# SCH_2-way_Traffic.net
KiCad netlist of a schematic drawn in Altium Designer
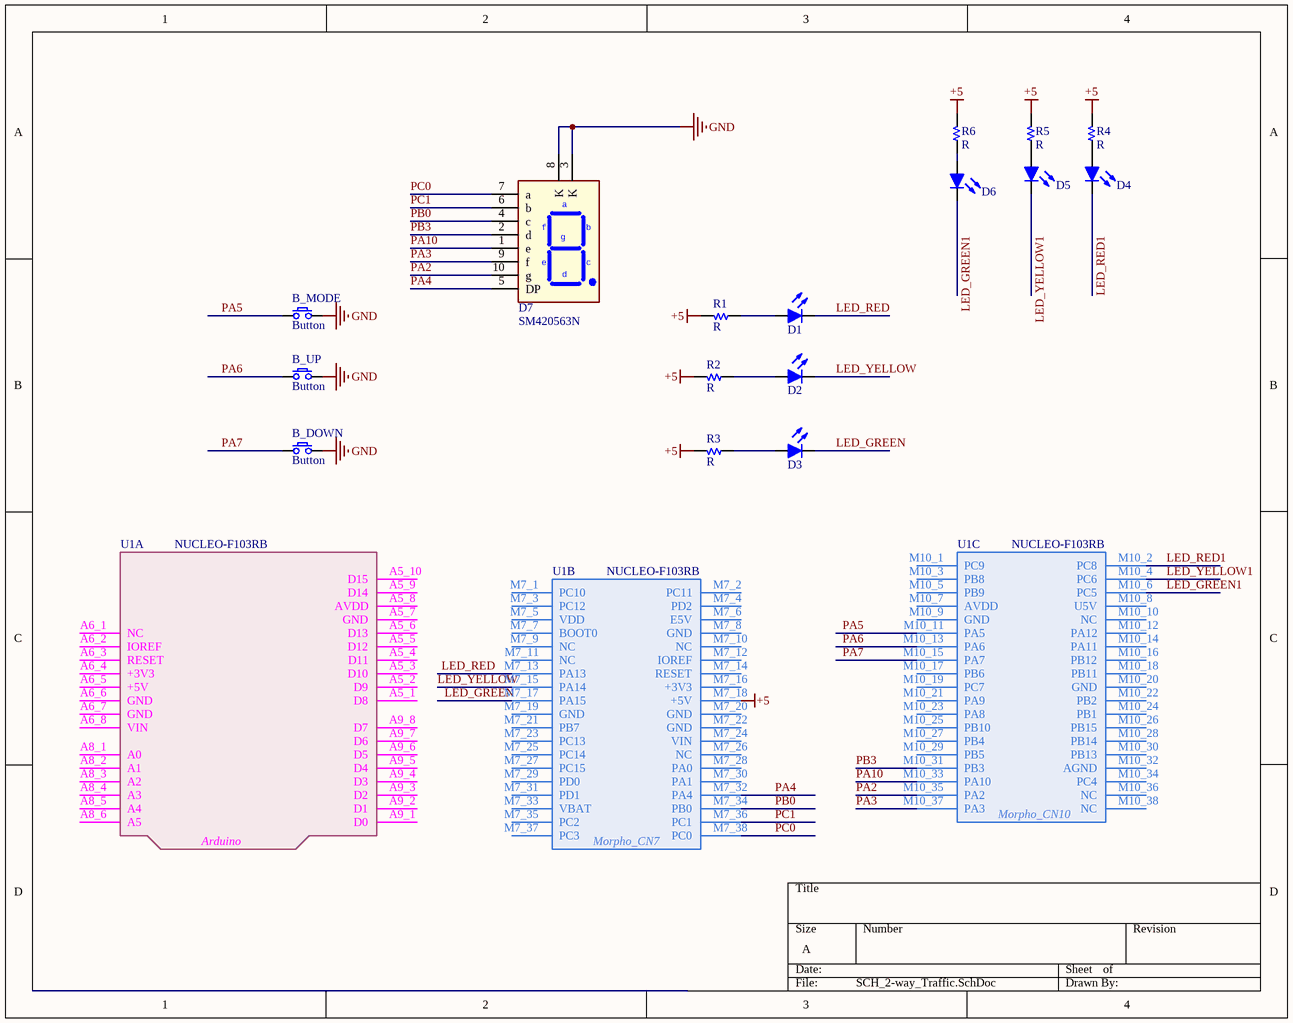
[diagram p0: SCH_2-way_Traffic.SchDoc]

(export (version "E")
  (design (tool "Eeschema 10.0.6"))
  (components
    (comp (ref "B_DOWN")
      (value "Button")
      (footprint "SW/2/DIP")
      (description "Tact switch 2 pin")
      (libsource (lib "chipfc_altium_libs") (part "SW SPST"))
    )
    (comp (ref "B_MODE")
      (value "Button")
      (footprint "SW/2/DIP")
      (description "Tact switch 2 pin")
      (libsource (lib "chipfc_altium_libs") (part "SW SPST"))
    )
    (comp (ref "B_UP")
      (value "Button")
      (footprint "SW/2/DIP")
      (description "Tact switch 2 pin")
      (libsource (lib "chipfc_altium_libs") (part "SW SPST"))
    )
    (comp (ref "D1")
      (value "Led")
      (footprint "LED 3MM - red")
      (description "Typical LED")
      (libsource (lib "chipfc_altium_libs") (part "Led"))
    )
    (comp (ref "D2")
      (value "Led")
      (footprint "LED 3MM - yellow")
      (description "Typical LED")
      (libsource (lib "chipfc_altium_libs") (part "Led"))
    )
    (comp (ref "D3")
      (value "Led")
      (footprint "LED 3MM - green")
      (description "Typical LED")
      (libsource (lib "chipfc_altium_libs") (part "Led"))
    )
    (comp (ref "D4")
      (value "Led")
      (footprint "LED 3MM - red")
      (description "Typical LED")
      (libsource (lib "chipfc_altium_libs") (part "Led"))
    )
    (comp (ref "D5")
      (value "Led")
      (footprint "LED 3MM - yellow")
      (description "Typical LED")
      (libsource (lib "chipfc_altium_libs") (part "Led"))
    )
    (comp (ref "D6")
      (value "Led")
      (footprint "LED 3MM - green")
      (description "Typical LED")
      (libsource (lib "chipfc_altium_libs") (part "Led"))
    )
    (comp (ref "D7")
      (value "SM420563N")
      (footprint "LED/7SEG/0.56")
      (description "SM420563N, Common-Cathode, LED 7-seg, RED, 0.56\",")
      (libsource (lib "bk2022") (part "LED 7-SEG SM420563N"))
    )
    (comp (ref "R1")
      (value "R")
      (footprint "R 0805")
      (description "Resistor")
      (libsource (lib "chipfc_altium_libs") (part "Resistor"))
    )
    (comp (ref "R2")
      (value "R")
      (footprint "R 0805")
      (description "Resistor")
      (libsource (lib "chipfc_altium_libs") (part "Resistor"))
    )
    (comp (ref "R3")
      (value "R")
      (footprint "R 0805")
      (description "Resistor")
      (libsource (lib "chipfc_altium_libs") (part "Resistor"))
    )
    (comp (ref "R4")
      (value "R")
      (footprint "R 0805")
      (description "Resistor")
      (libsource (lib "chipfc_altium_libs") (part "Resistor"))
    )
    (comp (ref "R5")
      (value "R")
      (footprint "R 0805")
      (description "Resistor")
      (libsource (lib "chipfc_altium_libs") (part "Resistor"))
    )
    (comp (ref "R6")
      (value "R")
      (footprint "R 0805")
      (description "Resistor")
      (libsource (lib "chipfc_altium_libs") (part "Resistor"))
    )
    (comp (ref "U1")
      (value "NUCLEO-F103RB")
      (footprint "NUCLEO")
      (fields (field (name "MANUFACTURER") "STMicroelectronics"))
      (libsource (lib "nucleo") (part "NUCLEO-F103RB"))
    )
  )
  (nets
    (net (code "1") (name "+5") (class "Default")
      (node (ref "R1") (pin "2") (pinfunction "2_2") (pintype "passive"))
      (node (ref "R2") (pin "2") (pinfunction "2_2") (pintype "passive"))
      (node (ref "R3") (pin "2") (pinfunction "2_2") (pintype "passive"))
      (node (ref "R4") (pin "2") (pinfunction "2_2") (pintype "passive"))
      (node (ref "R5") (pin "2") (pinfunction "2_2") (pintype "passive"))
      (node (ref "R6") (pin "2") (pinfunction "2_2") (pintype "passive"))
      (node (ref "U1") (pin "M7_18") (pinfunction "+5V_M7_18") (pintype "passive"))
    )
    (net (code "2") (name "/LED_GREEN") (class "Default")
      (node (ref "D3") (pin "2") (pinfunction "K_2") (pintype "passive"))
      (node (ref "U1") (pin "M7_17") (pinfunction "PA15_M7_17") (pintype "passive"))
    )
    (net (code "3") (name "/LED_GREEN1") (class "Default")
      (node (ref "D6") (pin "2") (pinfunction "K_2") (pintype "passive"))
      (node (ref "U1") (pin "M10_6") (pinfunction "PC5_M10_6") (pintype "passive"))
    )
    (net (code "4") (name "/LED_RED") (class "Default")
      (node (ref "D1") (pin "2") (pinfunction "K_2") (pintype "passive"))
      (node (ref "U1") (pin "M7_13") (pinfunction "PA13_M7_13") (pintype "passive"))
    )
    (net (code "5") (name "/LED_RED1") (class "Default")
      (node (ref "D4") (pin "2") (pinfunction "K_2") (pintype "passive"))
      (node (ref "U1") (pin "M10_2") (pinfunction "PC8_M10_2") (pintype "passive"))
    )
    (net (code "6") (name "/LED_YELLOW") (class "Default")
      (node (ref "D2") (pin "2") (pinfunction "K_2") (pintype "passive"))
      (node (ref "U1") (pin "M7_15") (pinfunction "PA14_M7_15") (pintype "passive"))
    )
    (net (code "7") (name "/LED_YELLOW1") (class "Default")
      (node (ref "D5") (pin "2") (pinfunction "K_2") (pintype "passive"))
      (node (ref "U1") (pin "M10_4") (pinfunction "PC6_M10_4") (pintype "passive"))
    )
    (net (code "8") (name "/PA2") (class "Default")
      (node (ref "D7") (pin "10") (pinfunction "g_10") (pintype "passive"))
      (node (ref "U1") (pin "M10_35") (pinfunction "PA2_M10_35") (pintype "passive"))
    )
    (net (code "9") (name "/PA3") (class "Default")
      (node (ref "D7") (pin "9") (pinfunction "f_9") (pintype "passive"))
      (node (ref "U1") (pin "M10_37") (pinfunction "PA3_M10_37") (pintype "passive"))
    )
    (net (code "10") (name "/PA4") (class "Default")
      (node (ref "D7") (pin "5") (pinfunction "DP_5") (pintype "passive"))
      (node (ref "U1") (pin "M7_32") (pinfunction "PA4_M7_32") (pintype "passive"))
    )
    (net (code "11") (name "/PA5") (class "Default")
      (node (ref "B_MODE") (pin "1") (pinfunction "1_1") (pintype "passive"))
      (node (ref "U1") (pin "M10_11") (pinfunction "PA5_M10_11") (pintype "passive"))
    )
    (net (code "12") (name "/PA6") (class "Default")
      (node (ref "B_UP") (pin "1") (pinfunction "1_1") (pintype "passive"))
      (node (ref "U1") (pin "M10_13") (pinfunction "PA6_M10_13") (pintype "passive"))
    )
    (net (code "13") (name "/PA7") (class "Default")
      (node (ref "B_DOWN") (pin "1") (pinfunction "1_1") (pintype "passive"))
      (node (ref "U1") (pin "M10_15") (pinfunction "PA7_M10_15") (pintype "passive"))
    )
    (net (code "14") (name "/PA10") (class "Default")
      (node (ref "D7") (pin "1") (pinfunction "e_1") (pintype "passive"))
      (node (ref "U1") (pin "M10_33") (pinfunction "PA10_M10_33") (pintype "passive"))
    )
    (net (code "15") (name "/PB0") (class "Default")
      (node (ref "D7") (pin "4") (pinfunction "c_4") (pintype "passive"))
      (node (ref "U1") (pin "M7_34") (pinfunction "PB0_M7_34") (pintype "passive"))
    )
    (net (code "16") (name "/PB3") (class "Default")
      (node (ref "D7") (pin "2") (pinfunction "d_2") (pintype "passive"))
      (node (ref "U1") (pin "M10_31") (pinfunction "PB3_M10_31") (pintype "passive"))
    )
    (net (code "17") (name "/PC0") (class "Default")
      (node (ref "D7") (pin "7") (pinfunction "a_7") (pintype "passive"))
      (node (ref "U1") (pin "M7_38") (pinfunction "PC0_M7_38") (pintype "passive"))
    )
    (net (code "18") (name "/PC1") (class "Default")
      (node (ref "D7") (pin "6") (pinfunction "b_6") (pintype "passive"))
      (node (ref "U1") (pin "M7_36") (pinfunction "PC1_M7_36") (pintype "passive"))
    )
    (net (code "19") (name "GND") (class "Default")
      (node (ref "B_DOWN") (pin "2") (pinfunction "2_2") (pintype "passive"))
      (node (ref "B_MODE") (pin "2") (pinfunction "2_2") (pintype "passive"))
      (node (ref "B_UP") (pin "2") (pinfunction "2_2") (pintype "passive"))
      (node (ref "D7") (pin "3") (pinfunction "K_3") (pintype "passive"))
      (node (ref "D7") (pin "8") (pinfunction "K_8") (pintype "passive"))
    )
    (net (code "20") (name "Net-(D1-A)") (class "Default")
      (node (ref "D1") (pin "1") (pinfunction "A_1") (pintype "passive"))
      (node (ref "R1") (pin "1") (pinfunction "1_1") (pintype "passive"))
    )
    (net (code "21") (name "Net-(D2-A)") (class "Default")
      (node (ref "D2") (pin "1") (pinfunction "A_1") (pintype "passive"))
      (node (ref "R2") (pin "1") (pinfunction "1_1") (pintype "passive"))
    )
    (net (code "22") (name "Net-(D3-A)") (class "Default")
      (node (ref "D3") (pin "1") (pinfunction "A_1") (pintype "passive"))
      (node (ref "R3") (pin "1") (pinfunction "1_1") (pintype "passive"))
    )
    (net (code "23") (name "Net-(D4-A)") (class "Default")
      (node (ref "D4") (pin "1") (pinfunction "A_1") (pintype "passive"))
      (node (ref "R4") (pin "1") (pinfunction "1_1") (pintype "passive"))
    )
    (net (code "24") (name "Net-(D5-A)") (class "Default")
      (node (ref "D5") (pin "1") (pinfunction "A_1") (pintype "passive"))
      (node (ref "R5") (pin "1") (pinfunction "1_1") (pintype "passive"))
    )
    (net (code "25") (name "Net-(D6-A)") (class "Default")
      (node (ref "D6") (pin "1") (pinfunction "A_1") (pintype "passive"))
      (node (ref "R6") (pin "1") (pinfunction "1_1") (pintype "passive"))
    )
    (net (code "26") (name "unconnected-(U1A-+3V3-PadA6_4)") (class "Default")
      (node (ref "U1") (pin "A6_4") (pinfunction "+3V3_A6_4") (pintype "passive"))
    )
    (net (code "27") (name "unconnected-(U1A-+5V-PadA6_5)") (class "Default")
      (node (ref "U1") (pin "A6_5") (pinfunction "+5V_A6_5") (pintype "passive"))
    )
    (net (code "28") (name "unconnected-(U1A-A0-PadA8_1)") (class "Default")
      (node (ref "U1") (pin "A8_1") (pinfunction "A0_A8_1") (pintype "passive"))
    )
    (net (code "29") (name "unconnected-(U1A-A1-PadA8_2)") (class "Default")
      (node (ref "U1") (pin "A8_2") (pinfunction "A1_A8_2") (pintype "passive"))
    )
    (net (code "30") (name "unconnected-(U1A-A2-PadA8_3)") (class "Default")
      (node (ref "U1") (pin "A8_3") (pinfunction "A2_A8_3") (pintype "passive"))
    )
    (net (code "31") (name "unconnected-(U1A-A3-PadA8_4)") (class "Default")
      (node (ref "U1") (pin "A8_4") (pinfunction "A3_A8_4") (pintype "passive"))
    )
    (net (code "32") (name "unconnected-(U1A-A4-PadA8_5)") (class "Default")
      (node (ref "U1") (pin "A8_5") (pinfunction "A4_A8_5") (pintype "passive"))
    )
    (net (code "33") (name "unconnected-(U1A-A5-PadA8_6)") (class "Default")
      (node (ref "U1") (pin "A8_6") (pinfunction "A5_A8_6") (pintype "passive"))
    )
    (net (code "34") (name "unconnected-(U1A-AVDD-PadA5_8)") (class "Default")
      (node (ref "U1") (pin "A5_8") (pinfunction "AVDD_A5_8") (pintype "passive"))
    )
    (net (code "35") (name "unconnected-(U1A-D0-PadA9_1)") (class "Default")
      (node (ref "U1") (pin "A9_1") (pinfunction "D0_A9_1") (pintype "passive"))
    )
    (net (code "36") (name "unconnected-(U1A-D1-PadA9_2)") (class "Default")
      (node (ref "U1") (pin "A9_2") (pinfunction "D1_A9_2") (pintype "passive"))
    )
    (net (code "37") (name "unconnected-(U1A-D2-PadA9_3)") (class "Default")
      (node (ref "U1") (pin "A9_3") (pinfunction "D2_A9_3") (pintype "passive"))
    )
    (net (code "38") (name "unconnected-(U1A-D3-PadA9_4)") (class "Default")
      (node (ref "U1") (pin "A9_4") (pinfunction "D3_A9_4") (pintype "passive"))
    )
    (net (code "39") (name "unconnected-(U1A-D4-PadA9_5)") (class "Default")
      (node (ref "U1") (pin "A9_5") (pinfunction "D4_A9_5") (pintype "passive"))
    )
    (net (code "40") (name "unconnected-(U1A-D5-PadA9_6)") (class "Default")
      (node (ref "U1") (pin "A9_6") (pinfunction "D5_A9_6") (pintype "passive"))
    )
    (net (code "41") (name "unconnected-(U1A-D6-PadA9_7)") (class "Default")
      (node (ref "U1") (pin "A9_7") (pinfunction "D6_A9_7") (pintype "passive"))
    )
    (net (code "42") (name "unconnected-(U1A-D7-PadA9_8)") (class "Default")
      (node (ref "U1") (pin "A9_8") (pinfunction "D7_A9_8") (pintype "passive"))
    )
    (net (code "43") (name "unconnected-(U1A-D8-PadA5_1)") (class "Default")
      (node (ref "U1") (pin "A5_1") (pinfunction "D8_A5_1") (pintype "passive"))
    )
    (net (code "44") (name "unconnected-(U1A-D9-PadA5_2)") (class "Default")
      (node (ref "U1") (pin "A5_2") (pinfunction "D9_A5_2") (pintype "passive"))
    )
    (net (code "45") (name "unconnected-(U1A-D10-PadA5_3)") (class "Default")
      (node (ref "U1") (pin "A5_3") (pinfunction "D10_A5_3") (pintype "passive"))
    )
    (net (code "46") (name "unconnected-(U1A-D11-PadA5_4)") (class "Default")
      (node (ref "U1") (pin "A5_4") (pinfunction "D11_A5_4") (pintype "passive"))
    )
    (net (code "47") (name "unconnected-(U1A-D12-PadA5_5)") (class "Default")
      (node (ref "U1") (pin "A5_5") (pinfunction "D12_A5_5") (pintype "passive"))
    )
    (net (code "48") (name "unconnected-(U1A-D13-PadA5_6)") (class "Default")
      (node (ref "U1") (pin "A5_6") (pinfunction "D13_A5_6") (pintype "passive"))
    )
    (net (code "49") (name "unconnected-(U1A-D14-PadA5_9)") (class "Default")
      (node (ref "U1") (pin "A5_9") (pinfunction "D14_A5_9") (pintype "passive"))
    )
    (net (code "50") (name "unconnected-(U1A-D15-PadA5_10)") (class "Default")
      (node (ref "U1") (pin "A5_10") (pinfunction "D15_A5_10") (pintype "passive"))
    )
    (net (code "51") (name "unconnected-(U1A-GND-PadA5_7)") (class "Default")
      (node (ref "U1") (pin "A5_7") (pinfunction "GND_A5_7") (pintype "passive"))
    )
    (net (code "52") (name "unconnected-(U1A-GND-PadA6_6)") (class "Default")
      (node (ref "U1") (pin "A6_6") (pinfunction "GND_A6_6") (pintype "passive"))
    )
    (net (code "53") (name "unconnected-(U1A-GND-PadA6_7)") (class "Default")
      (node (ref "U1") (pin "A6_7") (pinfunction "GND_A6_7") (pintype "passive"))
    )
    (net (code "54") (name "unconnected-(U1A-IOREF-PadA6_2)") (class "Default")
      (node (ref "U1") (pin "A6_2") (pinfunction "IOREF_A6_2") (pintype "passive"))
    )
    (net (code "55") (name "unconnected-(U1A-NC-PadA6_1)") (class "Default")
      (node (ref "U1") (pin "A6_1") (pinfunction "NC_A6_1") (pintype "passive"))
    )
    (net (code "56") (name "unconnected-(U1A-RESET-PadA6_3)") (class "Default")
      (node (ref "U1") (pin "A6_3") (pinfunction "RESET_A6_3") (pintype "passive"))
    )
    (net (code "57") (name "unconnected-(U1A-VIN-PadA6_8)") (class "Default")
      (node (ref "U1") (pin "A6_8") (pinfunction "VIN_A6_8") (pintype "passive"))
    )
    (net (code "58") (name "unconnected-(U1B-+3V3-PadM7_16)") (class "Default")
      (node (ref "U1") (pin "M7_16") (pinfunction "+3V3_M7_16") (pintype "passive"))
    )
    (net (code "59") (name "unconnected-(U1B-BOOT0-PadM7_7)") (class "Default")
      (node (ref "U1") (pin "M7_7") (pinfunction "BOOT0_M7_7") (pintype "passive"))
    )
    (net (code "60") (name "unconnected-(U1B-E5V-PadM7_6)") (class "Default")
      (node (ref "U1") (pin "M7_6") (pinfunction "E5V_M7_6") (pintype "passive"))
    )
    (net (code "61") (name "unconnected-(U1B-GND-PadM7_8)") (class "Default")
      (node (ref "U1") (pin "M7_8") (pinfunction "GND_M7_8") (pintype "passive"))
    )
    (net (code "62") (name "unconnected-(U1B-GND-PadM7_19)") (class "Default")
      (node (ref "U1") (pin "M7_19") (pinfunction "GND_M7_19") (pintype "passive"))
    )
    (net (code "63") (name "unconnected-(U1B-GND-PadM7_20)") (class "Default")
      (node (ref "U1") (pin "M7_20") (pinfunction "GND_M7_20") (pintype "passive"))
    )
    (net (code "64") (name "unconnected-(U1B-GND-PadM7_22)") (class "Default")
      (node (ref "U1") (pin "M7_22") (pinfunction "GND_M7_22") (pintype "passive"))
    )
    (net (code "65") (name "unconnected-(U1B-IOREF-PadM7_12)") (class "Default")
      (node (ref "U1") (pin "M7_12") (pinfunction "IOREF_M7_12") (pintype "passive"))
    )
    (net (code "66") (name "unconnected-(U1B-NC-PadM7_9)") (class "Default")
      (node (ref "U1") (pin "M7_9") (pinfunction "NC_M7_9") (pintype "passive"))
    )
    (net (code "67") (name "unconnected-(U1B-NC-PadM7_10)") (class "Default")
      (node (ref "U1") (pin "M7_10") (pinfunction "NC_M7_10") (pintype "passive"))
    )
    (net (code "68") (name "unconnected-(U1B-NC-PadM7_11)") (class "Default")
      (node (ref "U1") (pin "M7_11") (pinfunction "NC_M7_11") (pintype "passive"))
    )
    (net (code "69") (name "unconnected-(U1B-NC-PadM7_26)") (class "Default")
      (node (ref "U1") (pin "M7_26") (pinfunction "NC_M7_26") (pintype "passive"))
    )
    (net (code "70") (name "unconnected-(U1B-PA0-PadM7_28)") (class "Default")
      (node (ref "U1") (pin "M7_28") (pinfunction "PA0_M7_28") (pintype "passive"))
    )
    (net (code "71") (name "unconnected-(U1B-PA1-PadM7_30)") (class "Default")
      (node (ref "U1") (pin "M7_30") (pinfunction "PA1_M7_30") (pintype "passive"))
    )
    (net (code "72") (name "unconnected-(U1B-PB7-PadM7_21)") (class "Default")
      (node (ref "U1") (pin "M7_21") (pinfunction "PB7_M7_21") (pintype "passive"))
    )
    (net (code "73") (name "unconnected-(U1B-PC2-PadM7_35)") (class "Default")
      (node (ref "U1") (pin "M7_35") (pinfunction "PC2_M7_35") (pintype "passive"))
    )
    (net (code "74") (name "unconnected-(U1B-PC3-PadM7_37)") (class "Default")
      (node (ref "U1") (pin "M7_37") (pinfunction "PC3_M7_37") (pintype "passive"))
    )
    (net (code "75") (name "unconnected-(U1B-PC10-PadM7_1)") (class "Default")
      (node (ref "U1") (pin "M7_1") (pinfunction "PC10_M7_1") (pintype "passive"))
    )
    (net (code "76") (name "unconnected-(U1B-PC11-PadM7_2)") (class "Default")
      (node (ref "U1") (pin "M7_2") (pinfunction "PC11_M7_2") (pintype "passive"))
    )
    (net (code "77") (name "unconnected-(U1B-PC12-PadM7_3)") (class "Default")
      (node (ref "U1") (pin "M7_3") (pinfunction "PC12_M7_3") (pintype "passive"))
    )
    (net (code "78") (name "unconnected-(U1B-PC13-PadM7_23)") (class "Default")
      (node (ref "U1") (pin "M7_23") (pinfunction "PC13_M7_23") (pintype "passive"))
    )
    (net (code "79") (name "unconnected-(U1B-PC14-PadM7_25)") (class "Default")
      (node (ref "U1") (pin "M7_25") (pinfunction "PC14_M7_25") (pintype "passive"))
    )
    (net (code "80") (name "unconnected-(U1B-PC15-PadM7_27)") (class "Default")
      (node (ref "U1") (pin "M7_27") (pinfunction "PC15_M7_27") (pintype "passive"))
    )
    (net (code "81") (name "unconnected-(U1B-PD0-PadM7_29)") (class "Default")
      (node (ref "U1") (pin "M7_29") (pinfunction "PD0_M7_29") (pintype "passive"))
    )
    (net (code "82") (name "unconnected-(U1B-PD1-PadM7_31)") (class "Default")
      (node (ref "U1") (pin "M7_31") (pinfunction "PD1_M7_31") (pintype "passive"))
    )
    (net (code "83") (name "unconnected-(U1B-PD2-PadM7_4)") (class "Default")
      (node (ref "U1") (pin "M7_4") (pinfunction "PD2_M7_4") (pintype "passive"))
    )
    (net (code "84") (name "unconnected-(U1B-RESET-PadM7_14)") (class "Default")
      (node (ref "U1") (pin "M7_14") (pinfunction "RESET_M7_14") (pintype "passive"))
    )
    (net (code "85") (name "unconnected-(U1B-VBAT-PadM7_33)") (class "Default")
      (node (ref "U1") (pin "M7_33") (pinfunction "VBAT_M7_33") (pintype "passive"))
    )
    (net (code "86") (name "unconnected-(U1B-VDD-PadM7_5)") (class "Default")
      (node (ref "U1") (pin "M7_5") (pinfunction "VDD_M7_5") (pintype "passive"))
    )
    (net (code "87") (name "unconnected-(U1B-VIN-PadM7_24)") (class "Default")
      (node (ref "U1") (pin "M7_24") (pinfunction "VIN_M7_24") (pintype "passive"))
    )
    (net (code "88") (name "unconnected-(U1C-AGND-PadM10_32)") (class "Default")
      (node (ref "U1") (pin "M10_32") (pinfunction "AGND_M10_32") (pintype "passive"))
    )
    (net (code "89") (name "unconnected-(U1C-AVDD-PadM10_7)") (class "Default")
      (node (ref "U1") (pin "M10_7") (pinfunction "AVDD_M10_7") (pintype "passive"))
    )
    (net (code "90") (name "unconnected-(U1C-GND-PadM10_9)") (class "Default")
      (node (ref "U1") (pin "M10_9") (pinfunction "GND_M10_9") (pintype "passive"))
    )
    (net (code "91") (name "unconnected-(U1C-GND-PadM10_20)") (class "Default")
      (node (ref "U1") (pin "M10_20") (pinfunction "GND_M10_20") (pintype "passive"))
    )
    (net (code "92") (name "unconnected-(U1C-NC-PadM10_10)") (class "Default")
      (node (ref "U1") (pin "M10_10") (pinfunction "NC_M10_10") (pintype "passive"))
    )
    (net (code "93") (name "unconnected-(U1C-NC-PadM10_36)") (class "Default")
      (node (ref "U1") (pin "M10_36") (pinfunction "NC_M10_36") (pintype "passive"))
    )
    (net (code "94") (name "unconnected-(U1C-NC-PadM10_38)") (class "Default")
      (node (ref "U1") (pin "M10_38") (pinfunction "NC_M10_38") (pintype "passive"))
    )
    (net (code "95") (name "unconnected-(U1C-PA8-PadM10_23)") (class "Default")
      (node (ref "U1") (pin "M10_23") (pinfunction "PA8_M10_23") (pintype "passive"))
    )
    (net (code "96") (name "unconnected-(U1C-PA9-PadM10_21)") (class "Default")
      (node (ref "U1") (pin "M10_21") (pinfunction "PA9_M10_21") (pintype "passive"))
    )
    (net (code "97") (name "unconnected-(U1C-PA11-PadM10_14)") (class "Default")
      (node (ref "U1") (pin "M10_14") (pinfunction "PA11_M10_14") (pintype "passive"))
    )
    (net (code "98") (name "unconnected-(U1C-PA12-PadM10_12)") (class "Default")
      (node (ref "U1") (pin "M10_12") (pinfunction "PA12_M10_12") (pintype "passive"))
    )
    (net (code "99") (name "unconnected-(U1C-PB1-PadM10_24)") (class "Default")
      (node (ref "U1") (pin "M10_24") (pinfunction "PB1_M10_24") (pintype "passive"))
    )
    (net (code "100") (name "unconnected-(U1C-PB2-PadM10_22)") (class "Default")
      (node (ref "U1") (pin "M10_22") (pinfunction "PB2_M10_22") (pintype "passive"))
    )
    (net (code "101") (name "unconnected-(U1C-PB4-PadM10_27)") (class "Default")
      (node (ref "U1") (pin "M10_27") (pinfunction "PB4_M10_27") (pintype "passive"))
    )
    (net (code "102") (name "unconnected-(U1C-PB5-PadM10_29)") (class "Default")
      (node (ref "U1") (pin "M10_29") (pinfunction "PB5_M10_29") (pintype "passive"))
    )
    (net (code "103") (name "unconnected-(U1C-PB6-PadM10_17)") (class "Default")
      (node (ref "U1") (pin "M10_17") (pinfunction "PB6_M10_17") (pintype "passive"))
    )
    (net (code "104") (name "unconnected-(U1C-PB8-PadM10_3)") (class "Default")
      (node (ref "U1") (pin "M10_3") (pinfunction "PB8_M10_3") (pintype "passive"))
    )
    (net (code "105") (name "unconnected-(U1C-PB9-PadM10_5)") (class "Default")
      (node (ref "U1") (pin "M10_5") (pinfunction "PB9_M10_5") (pintype "passive"))
    )
    (net (code "106") (name "unconnected-(U1C-PB10-PadM10_25)") (class "Default")
      (node (ref "U1") (pin "M10_25") (pinfunction "PB10_M10_25") (pintype "passive"))
    )
    (net (code "107") (name "unconnected-(U1C-PB11-PadM10_18)") (class "Default")
      (node (ref "U1") (pin "M10_18") (pinfunction "PB11_M10_18") (pintype "passive"))
    )
    (net (code "108") (name "unconnected-(U1C-PB12-PadM10_16)") (class "Default")
      (node (ref "U1") (pin "M10_16") (pinfunction "PB12_M10_16") (pintype "passive"))
    )
    (net (code "109") (name "unconnected-(U1C-PB13-PadM10_30)") (class "Default")
      (node (ref "U1") (pin "M10_30") (pinfunction "PB13_M10_30") (pintype "passive"))
    )
    (net (code "110") (name "unconnected-(U1C-PB14-PadM10_28)") (class "Default")
      (node (ref "U1") (pin "M10_28") (pinfunction "PB14_M10_28") (pintype "passive"))
    )
    (net (code "111") (name "unconnected-(U1C-PB15-PadM10_26)") (class "Default")
      (node (ref "U1") (pin "M10_26") (pinfunction "PB15_M10_26") (pintype "passive"))
    )
    (net (code "112") (name "unconnected-(U1C-PC4-PadM10_34)") (class "Default")
      (node (ref "U1") (pin "M10_34") (pinfunction "PC4_M10_34") (pintype "passive"))
    )
    (net (code "113") (name "unconnected-(U1C-PC7-PadM10_19)") (class "Default")
      (node (ref "U1") (pin "M10_19") (pinfunction "PC7_M10_19") (pintype "passive"))
    )
    (net (code "114") (name "unconnected-(U1C-PC9-PadM10_1)") (class "Default")
      (node (ref "U1") (pin "M10_1") (pinfunction "PC9_M10_1") (pintype "passive"))
    )
    (net (code "115") (name "unconnected-(U1C-U5V-PadM10_8)") (class "Default")
      (node (ref "U1") (pin "M10_8") (pinfunction "U5V_M10_8") (pintype "passive"))
    )
  )
)
